# Interfaces.net
KiCad netlist of a schematic drawn in Altium Designer
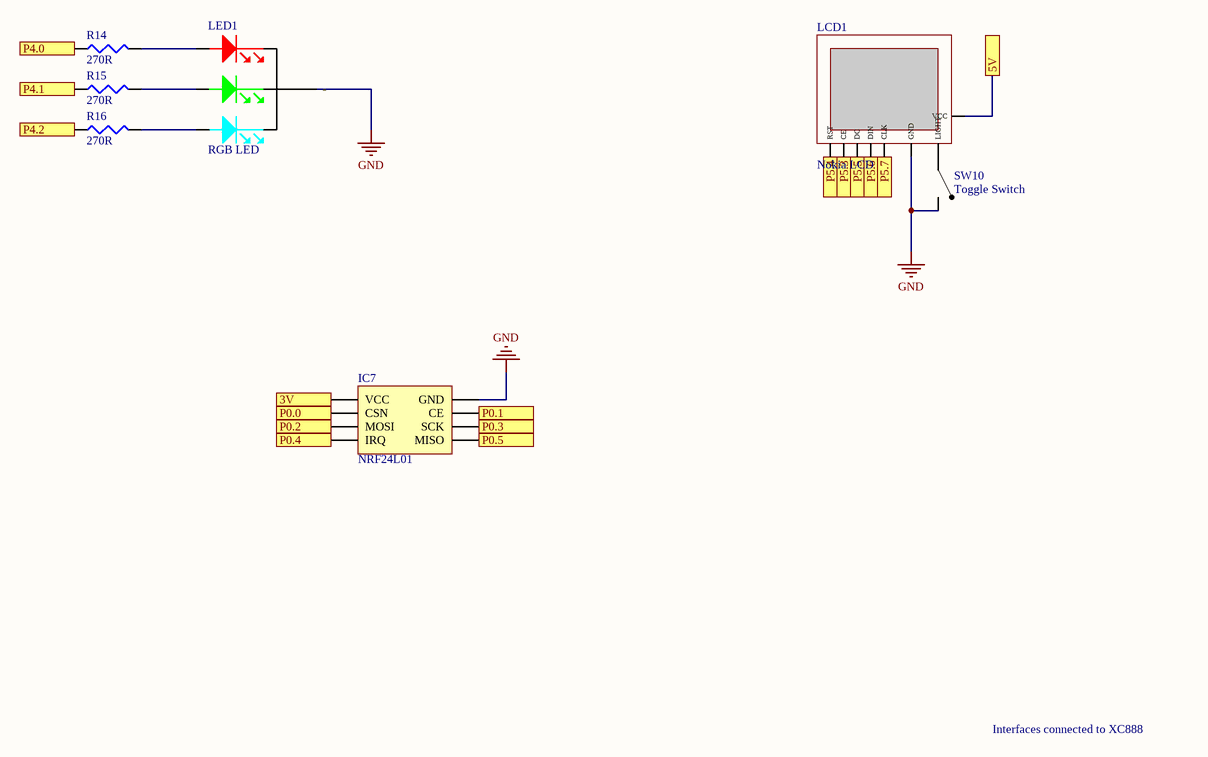
[diagram p0: Interfaces.SchDoc]

(export (version "E")
  (design (tool "Eeschema 10.0.6"))
  (components
    (comp (ref "IC7")
      (value "NRF24L01")
      (footprint "NRF header")
      (libsource (lib "Tama_Schlib") (part "NRF24L01 Module"))
    )
    (comp (ref "LCD1")
      (value "Nokia LCD")
      (footprint "LCD header")
      (description "Nokia 5110 LCD")
      (libsource (lib "Tama_Schlib") (part "Nokia 5110 LCD"))
    )
    (comp (ref "LED1")
      (value "RGB LED")
      (footprint "4 PIN - RGB LED")
      (description "Hyper Red/Green/Blue 50º Water Clear Full Color LED Lamp - T-1 3/4")
      (fields
        (field (name "MANUFACTURER") "Kingbright")
        (field (name "MANUFACTURER PART NUMBER") "WP154A4SUREQBFZGC")
      )
      (libsource (lib "Tama_Schlib") (part "WP154A4SUREQBFZGC"))
    )
    (comp (ref "R14")
      (value "270R")
      (footprint "CRG0402F")
      (description "Res Thick Film 0402 270 Ohm 1% 0.063W(1/16W) ±100ppm/C Pad SMD T/R")
      (fields
        (field (name "MANUFACTURER") "TE Connectivity")
        (field (name "MANUFACTURER PART NUMBER") "CRG0402F270R")
      )
      (libsource (lib "Tama_Schlib") (part "CRG0402F270R"))
    )
    (comp (ref "R15")
      (value "270R")
      (footprint "CRG0402F")
      (description "Res Thick Film 0402 270 Ohm 1% 0.063W(1/16W) ±100ppm/C Pad SMD T/R")
      (fields
        (field (name "MANUFACTURER") "TE Connectivity")
        (field (name "MANUFACTURER PART NUMBER") "CRG0402F270R")
      )
      (libsource (lib "Tama_Schlib") (part "CRG0402F270R"))
    )
    (comp (ref "R16")
      (value "270R")
      (footprint "CRG0402F")
      (description "Res Thick Film 0402 270 Ohm 1% 0.063W(1/16W) ±100ppm/C Pad SMD T/R")
      (fields
        (field (name "MANUFACTURER") "TE Connectivity")
        (field (name "MANUFACTURER PART NUMBER") "CRG0402F270R")
      )
      (libsource (lib "Tama_Schlib") (part "CRG0402F270R"))
    )
    (comp (ref "SW10")
      (value "Toggle Switch")
      (footprint "SMD Switch")
      (description "C&K SK-12D07-VG 3 NS Switches > Slide > Miniature > Mini R/A Slide")
      (fields
        (field (name "MANUFACTURER") "ITT C&K")
        (field (name "MANUFACTURER PART NUMBER") "SK12D07VG3NS")
      )
      (libsource (lib "Tama_Schlib") (part "SK12D07VG3NS"))
    )
  )
  (nets
    (net (code "1") (name "/3V") (class "Default")
      (node (ref "IC7") (pin "1") (pinfunction "VCC_1") (pintype "passive"))
    )
    (net (code "2") (name "/5V") (class "Default")
      (node (ref "LCD1") (pin "6") (pinfunction "VCC_6") (pintype "passive"))
    )
    (net (code "3") (name "/P0.0") (class "Default")
      (node (ref "IC7") (pin "3") (pinfunction "CSN_3") (pintype "passive"))
    )
    (net (code "4") (name "/P0.1") (class "Default")
      (node (ref "IC7") (pin "4") (pinfunction "CE_4") (pintype "passive"))
    )
    (net (code "5") (name "/P0.2") (class "Default")
      (node (ref "IC7") (pin "5") (pinfunction "MOSI_5") (pintype "passive"))
    )
    (net (code "6") (name "/P0.3") (class "Default")
      (node (ref "IC7") (pin "6") (pinfunction "SCK_6") (pintype "passive"))
    )
    (net (code "7") (name "/P0.4") (class "Default")
      (node (ref "IC7") (pin "7") (pinfunction "IRQ_7") (pintype "passive"))
    )
    (net (code "8") (name "/P0.5") (class "Default")
      (node (ref "IC7") (pin "8") (pinfunction "MISO_8") (pintype "passive"))
    )
    (net (code "9") (name "/P4.0") (class "Default")
      (node (ref "R14") (pin "1") (pinfunction "1_1") (pintype "passive"))
    )
    (net (code "10") (name "/P4.1") (class "Default")
      (node (ref "R15") (pin "1") (pinfunction "1_1") (pintype "passive"))
    )
    (net (code "11") (name "/P4.2") (class "Default")
      (node (ref "R16") (pin "1") (pinfunction "1_1") (pintype "passive"))
    )
    (net (code "12") (name "/P5.3") (class "Default")
      (node (ref "LCD1") (pin "2") (pinfunction "CE_2") (pintype "passive"))
    )
    (net (code "13") (name "/P5.4") (class "Default")
      (node (ref "LCD1") (pin "1") (pinfunction "RST_1") (pintype "passive"))
    )
    (net (code "14") (name "/P5.5") (class "Default")
      (node (ref "LCD1") (pin "3") (pinfunction "DC_3") (pintype "passive"))
    )
    (net (code "15") (name "/P5.6") (class "Default")
      (node (ref "LCD1") (pin "4") (pinfunction "DIN_4") (pintype "passive"))
    )
    (net (code "16") (name "/P5.7") (class "Default")
      (node (ref "LCD1") (pin "5") (pinfunction "CLK_5") (pintype "passive"))
    )
    (net (code "17") (name "GND") (class "Default")
      (node (ref "IC7") (pin "2") (pinfunction "GND_2") (pintype "passive"))
      (node (ref "LCD1") (pin "8") (pinfunction "GND_8") (pintype "passive"))
      (node (ref "LED1") (pin "2") (pinfunction "-_2") (pintype "passive"))
      (node (ref "SW10") (pin "2") (pinfunction "2_2") (pintype "passive"))
    )
    (net (code "18") (name "Net-(LCD1-LIGHT)") (class "Default")
      (node (ref "LCD1") (pin "7") (pinfunction "LIGHT_7") (pintype "passive"))
      (node (ref "SW10") (pin "1") (pinfunction "1_1") (pintype "passive"))
    )
    (net (code "19") (name "Net-(LED1-Pad1)") (class "Default")
      (node (ref "LED1") (pin "1") (pinfunction "1_1") (pintype "passive"))
      (node (ref "R16") (pin "2") (pinfunction "2_2") (pintype "passive"))
    )
    (net (code "20") (name "Net-(LED1-Pad3)") (class "Default")
      (node (ref "LED1") (pin "3") (pinfunction "3_3") (pintype "passive"))
      (node (ref "R15") (pin "2") (pinfunction "2_2") (pintype "passive"))
    )
    (net (code "21") (name "Net-(LED1-Pad4)") (class "Default")
      (node (ref "LED1") (pin "4") (pinfunction "4_4") (pintype "passive"))
      (node (ref "R14") (pin "2") (pinfunction "2_2") (pintype "passive"))
    )
  )
)
